# Sheet1.net
KiCad netlist of a schematic drawn in Altium Designer
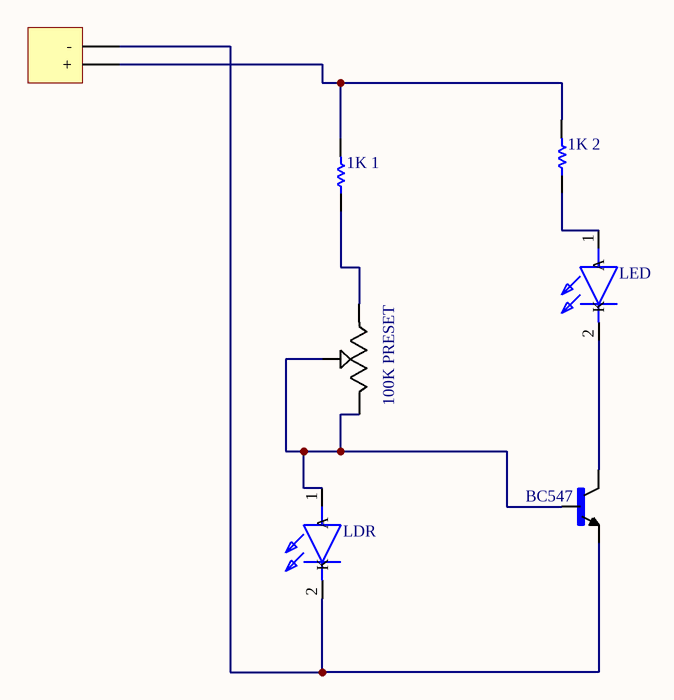
[diagram p0: Sheet1.SchDoc]

(export (version "E")
  (design (tool "Eeschema 10.0.6"))
  (components
    (comp (ref "1K 1")
      (value "Res1")
      (footprint "AXIAL-0.3")
      (description "Resistor")
      (fields (field (name "PUBLISHER") "Altium Limited"))
      (libsource (lib "Miscellaneous Devices") (part "Res1"))
    )
    (comp (ref "1K 2")
      (value "Res1")
      (footprint "AXIAL-0.3")
      (description "Resistor")
      (fields (field (name "PUBLISHER") "Altium Limited"))
      (libsource (lib "Miscellaneous Devices") (part "Res1"))
    )
    (comp (ref "100K PRESET")
      (value "~")
      (footprint "*TRIM_EVN-D8AA03B14")
      (description "Trimmer; Carbon; Rest 10 Kilohms; PCB; 1 Turn; Pwr-Rtg 0.1 W; Linear; Top Adj; 6 mm SQ")
      (fields (field (name "MF") "Panasonic Electronic") (field (name "MP") "EVN-D8AA03B14"))
      (libsource (lib "EVN-D8AA03B14") (part "EVN-D8AA03B14"))
    )
    (comp (ref "BC547")
      (value "BC547*")
      (footprint "*TO92")
      (description "Transistor NPN BC547 PHILIPS miliampere=100 TO92")
      (fields (field (name "MP") "BC547") (field (name "MF") "ON Semiconductor"))
      (libsource (lib "BC547_") (part "BC547*"))
    )
    (comp (ref "LDR")
      (value "L-53GD")
      (footprint "SamacSys:L-53GD")
      (description "LED")
      (fields (field (name "RS PART NUMBER") "2286004A"))
      (libsource (lib "SamacSys") (part "L-53GD"))
    )
    (comp (ref "LED")
      (value "L-53GD")
      (footprint "SamacSys:L-53GD")
      (description "LED")
      (fields (field (name "RS PART NUMBER") "2286004A"))
      (libsource (lib "SamacSys") (part "L-53GD"))
    )
    (comp (ref "P1")
      (value "Header 2")
      (footprint "HDR1X2")
      (description "Header, 2-Pin")
      (fields (field (name "PUBLISHER") "Altium Limited"))
      (libsource (lib "Miscellaneous Connectors") (part "Header 2"))
    )
  )
  (nets
    (net (code "1") (name "Net-(100K PRESET-Pad1)") (class "Default")
      (node (ref "100K PRESET") (pin "1") (pinfunction "1_1") (pintype "passive"))
      (node (ref "1K 1") (pin "1") (pinfunction "1_1") (pintype "passive"))
    )
    (net (code "2") (name "Net-(BC547-B)") (class "Default")
      (node (ref "100K PRESET") (pin "2") (pinfunction "2_2") (pintype "passive"))
      (node (ref "100K PRESET") (pin "3") (pinfunction "3_3") (pintype "passive"))
      (node (ref "BC547") (pin "2") (pinfunction "B_2") (pintype "passive"))
      (node (ref "LDR") (pin "1") (pinfunction "A_1") (pintype "passive"))
    )
    (net (code "3") (name "Net-(BC547-C)") (class "Default")
      (node (ref "BC547") (pin "1") (pinfunction "C_1") (pintype "passive"))
      (node (ref "LED") (pin "2") (pinfunction "K_2") (pintype "passive"))
    )
    (net (code "4") (name "Net-(BC547-E)") (class "Default")
      (node (ref "BC547") (pin "3") (pinfunction "E_3") (pintype "passive"))
      (node (ref "LDR") (pin "2") (pinfunction "K_2") (pintype "passive"))
      (node (ref "P1") (pin "2") (pinfunction "-_2") (pintype "passive"))
    )
    (net (code "5") (name "Net-(LED-A)") (class "Default")
      (node (ref "1K 2") (pin "1") (pinfunction "1_1") (pintype "passive"))
      (node (ref "LED") (pin "1") (pinfunction "A_1") (pintype "passive"))
    )
    (net (code "6") (name "Net-(P1-+)") (class "Default")
      (node (ref "1K 1") (pin "2") (pinfunction "2_2") (pintype "passive"))
      (node (ref "1K 2") (pin "2") (pinfunction "2_2") (pintype "passive"))
      (node (ref "P1") (pin "1") (pinfunction "+_1") (pintype "passive"))
    )
  )
)
